# 03_Connectors.net
KiCad netlist of a schematic drawn in Altium Designer
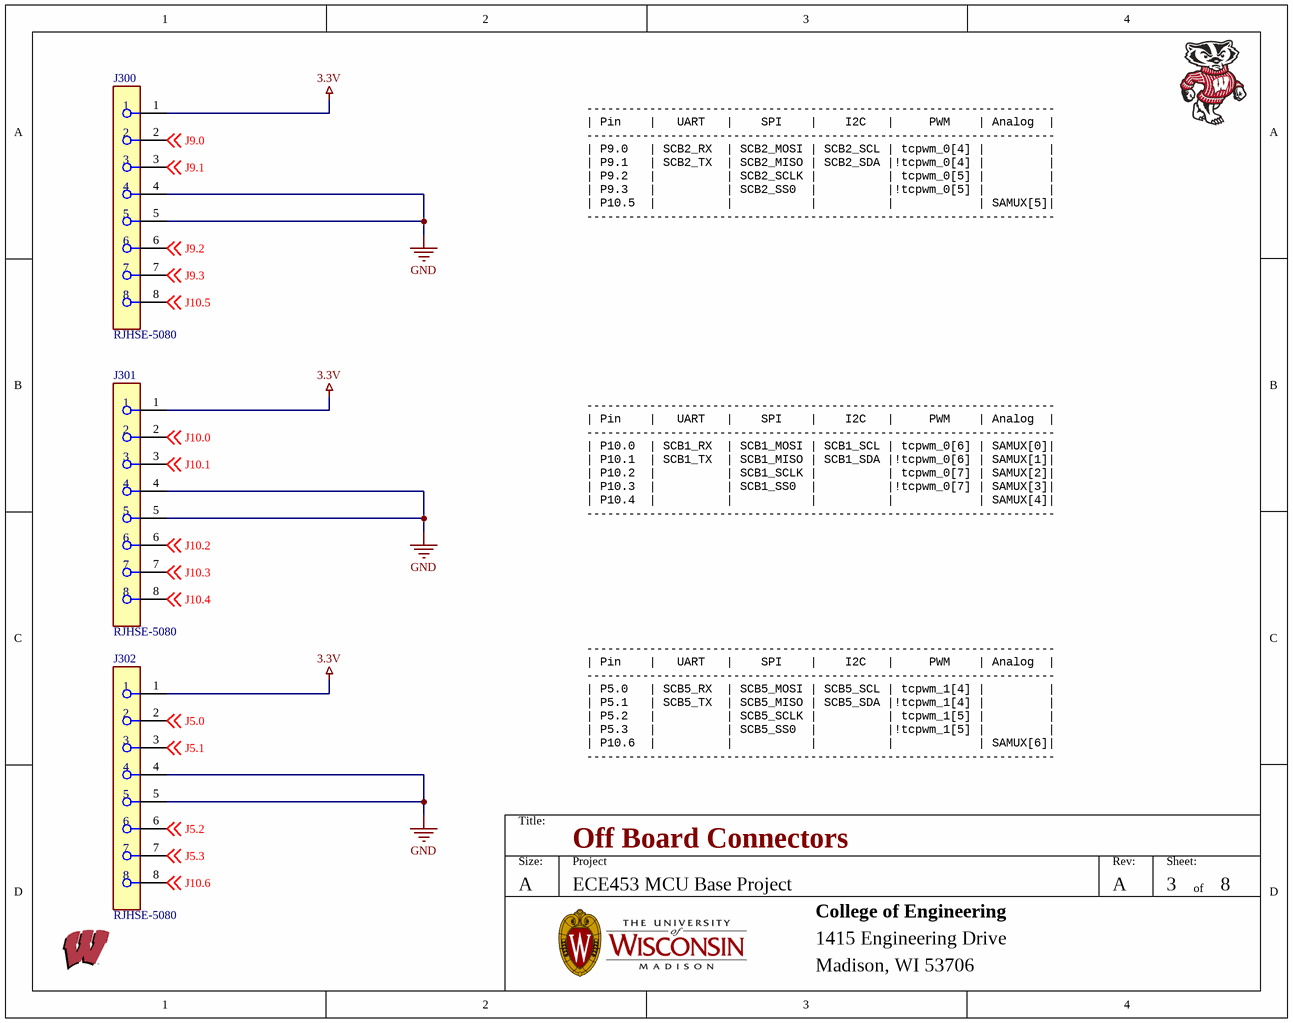
[diagram p0: 03_Connectors.SchDoc]

(export (version "E")
  (design (tool "Eeschema 10.0.6"))
  (components
    (comp (ref "J300")
      (value "RJHSE-5080")
      (footprint "FP-RJHSE-5080-MFG")
      (description "CONN MOD JACK 8P8C R/A UNSHLD")
      (fields
        (field (name "OCTOPART") "https://octopart.com/rjhse-5080-amphenol-45060")
        (field (name "MANUFACTURER") "Amphenol")
      )
      (libsource (lib "Altium Content Vault") (part "b0a0b555dd3abf3683e7c330df25cc4"))
    )
    (comp (ref "J301")
      (value "RJHSE-5080")
      (footprint "FP-RJHSE-5080-MFG")
      (description "CONN MOD JACK 8P8C R/A UNSHLD")
      (fields
        (field (name "OCTOPART") "https://octopart.com/rjhse-5080-amphenol-45060")
        (field (name "MANUFACTURER") "Amphenol")
      )
      (libsource (lib "Altium Content Vault") (part "b0a0b555dd3abf3683e7c330df25cc4"))
    )
    (comp (ref "J302")
      (value "RJHSE-5080")
      (footprint "FP-RJHSE-5080-MFG")
      (description "CONN MOD JACK 8P8C R/A UNSHLD")
      (fields
        (field (name "OCTOPART") "https://octopart.com/rjhse-5080-amphenol-45060")
        (field (name "MANUFACTURER") "Amphenol")
      )
      (libsource (lib "Altium Content Vault") (part "b0a0b555dd3abf3683e7c330df25cc4"))
    )
  )
  (nets
    (net (code "1") (name "3.3V") (class "Default")
      (node (ref "J300") (pin "1") (pinfunction "1_1") (pintype "passive"))
      (node (ref "J301") (pin "1") (pinfunction "1_1") (pintype "passive"))
      (node (ref "J302") (pin "1") (pinfunction "1_1") (pintype "passive"))
    )
    (net (code "2") (name "GND") (class "Default")
      (node (ref "J300") (pin "4") (pinfunction "4_4") (pintype "passive"))
      (node (ref "J300") (pin "5") (pinfunction "5_5") (pintype "passive"))
      (node (ref "J301") (pin "4") (pinfunction "4_4") (pintype "passive"))
      (node (ref "J301") (pin "5") (pinfunction "5_5") (pintype "passive"))
      (node (ref "J302") (pin "4") (pinfunction "4_4") (pintype "passive"))
      (node (ref "J302") (pin "5") (pinfunction "5_5") (pintype "passive"))
    )
    (net (code "3") (name "J5.0") (class "Default")
      (node (ref "J302") (pin "2") (pinfunction "2_2") (pintype "passive"))
    )
    (net (code "4") (name "J5.1") (class "Default")
      (node (ref "J302") (pin "3") (pinfunction "3_3") (pintype "passive"))
    )
    (net (code "5") (name "J5.2") (class "Default")
      (node (ref "J302") (pin "6") (pinfunction "6_6") (pintype "passive"))
    )
    (net (code "6") (name "J5.3") (class "Default")
      (node (ref "J302") (pin "7") (pinfunction "7_7") (pintype "passive"))
    )
    (net (code "7") (name "J9.0") (class "Default")
      (node (ref "J300") (pin "2") (pinfunction "2_2") (pintype "passive"))
    )
    (net (code "8") (name "J9.1") (class "Default")
      (node (ref "J300") (pin "3") (pinfunction "3_3") (pintype "passive"))
    )
    (net (code "9") (name "J9.2") (class "Default")
      (node (ref "J300") (pin "6") (pinfunction "6_6") (pintype "passive"))
    )
    (net (code "10") (name "J9.3") (class "Default")
      (node (ref "J300") (pin "7") (pinfunction "7_7") (pintype "passive"))
    )
    (net (code "11") (name "J10.0") (class "Default")
      (node (ref "J301") (pin "2") (pinfunction "2_2") (pintype "passive"))
    )
    (net (code "12") (name "J10.1") (class "Default")
      (node (ref "J301") (pin "3") (pinfunction "3_3") (pintype "passive"))
    )
    (net (code "13") (name "J10.2") (class "Default")
      (node (ref "J301") (pin "6") (pinfunction "6_6") (pintype "passive"))
    )
    (net (code "14") (name "J10.3") (class "Default")
      (node (ref "J301") (pin "7") (pinfunction "7_7") (pintype "passive"))
    )
    (net (code "15") (name "J10.4") (class "Default")
      (node (ref "J301") (pin "8") (pinfunction "8_8") (pintype "passive"))
    )
    (net (code "16") (name "J10.5") (class "Default")
      (node (ref "J300") (pin "8") (pinfunction "8_8") (pintype "passive"))
    )
    (net (code "17") (name "J10.6") (class "Default")
      (node (ref "J302") (pin "8") (pinfunction "8_8") (pintype "passive"))
    )
  )
)
